# PT100.net
KiCad netlist of a schematic drawn in Altium Designer
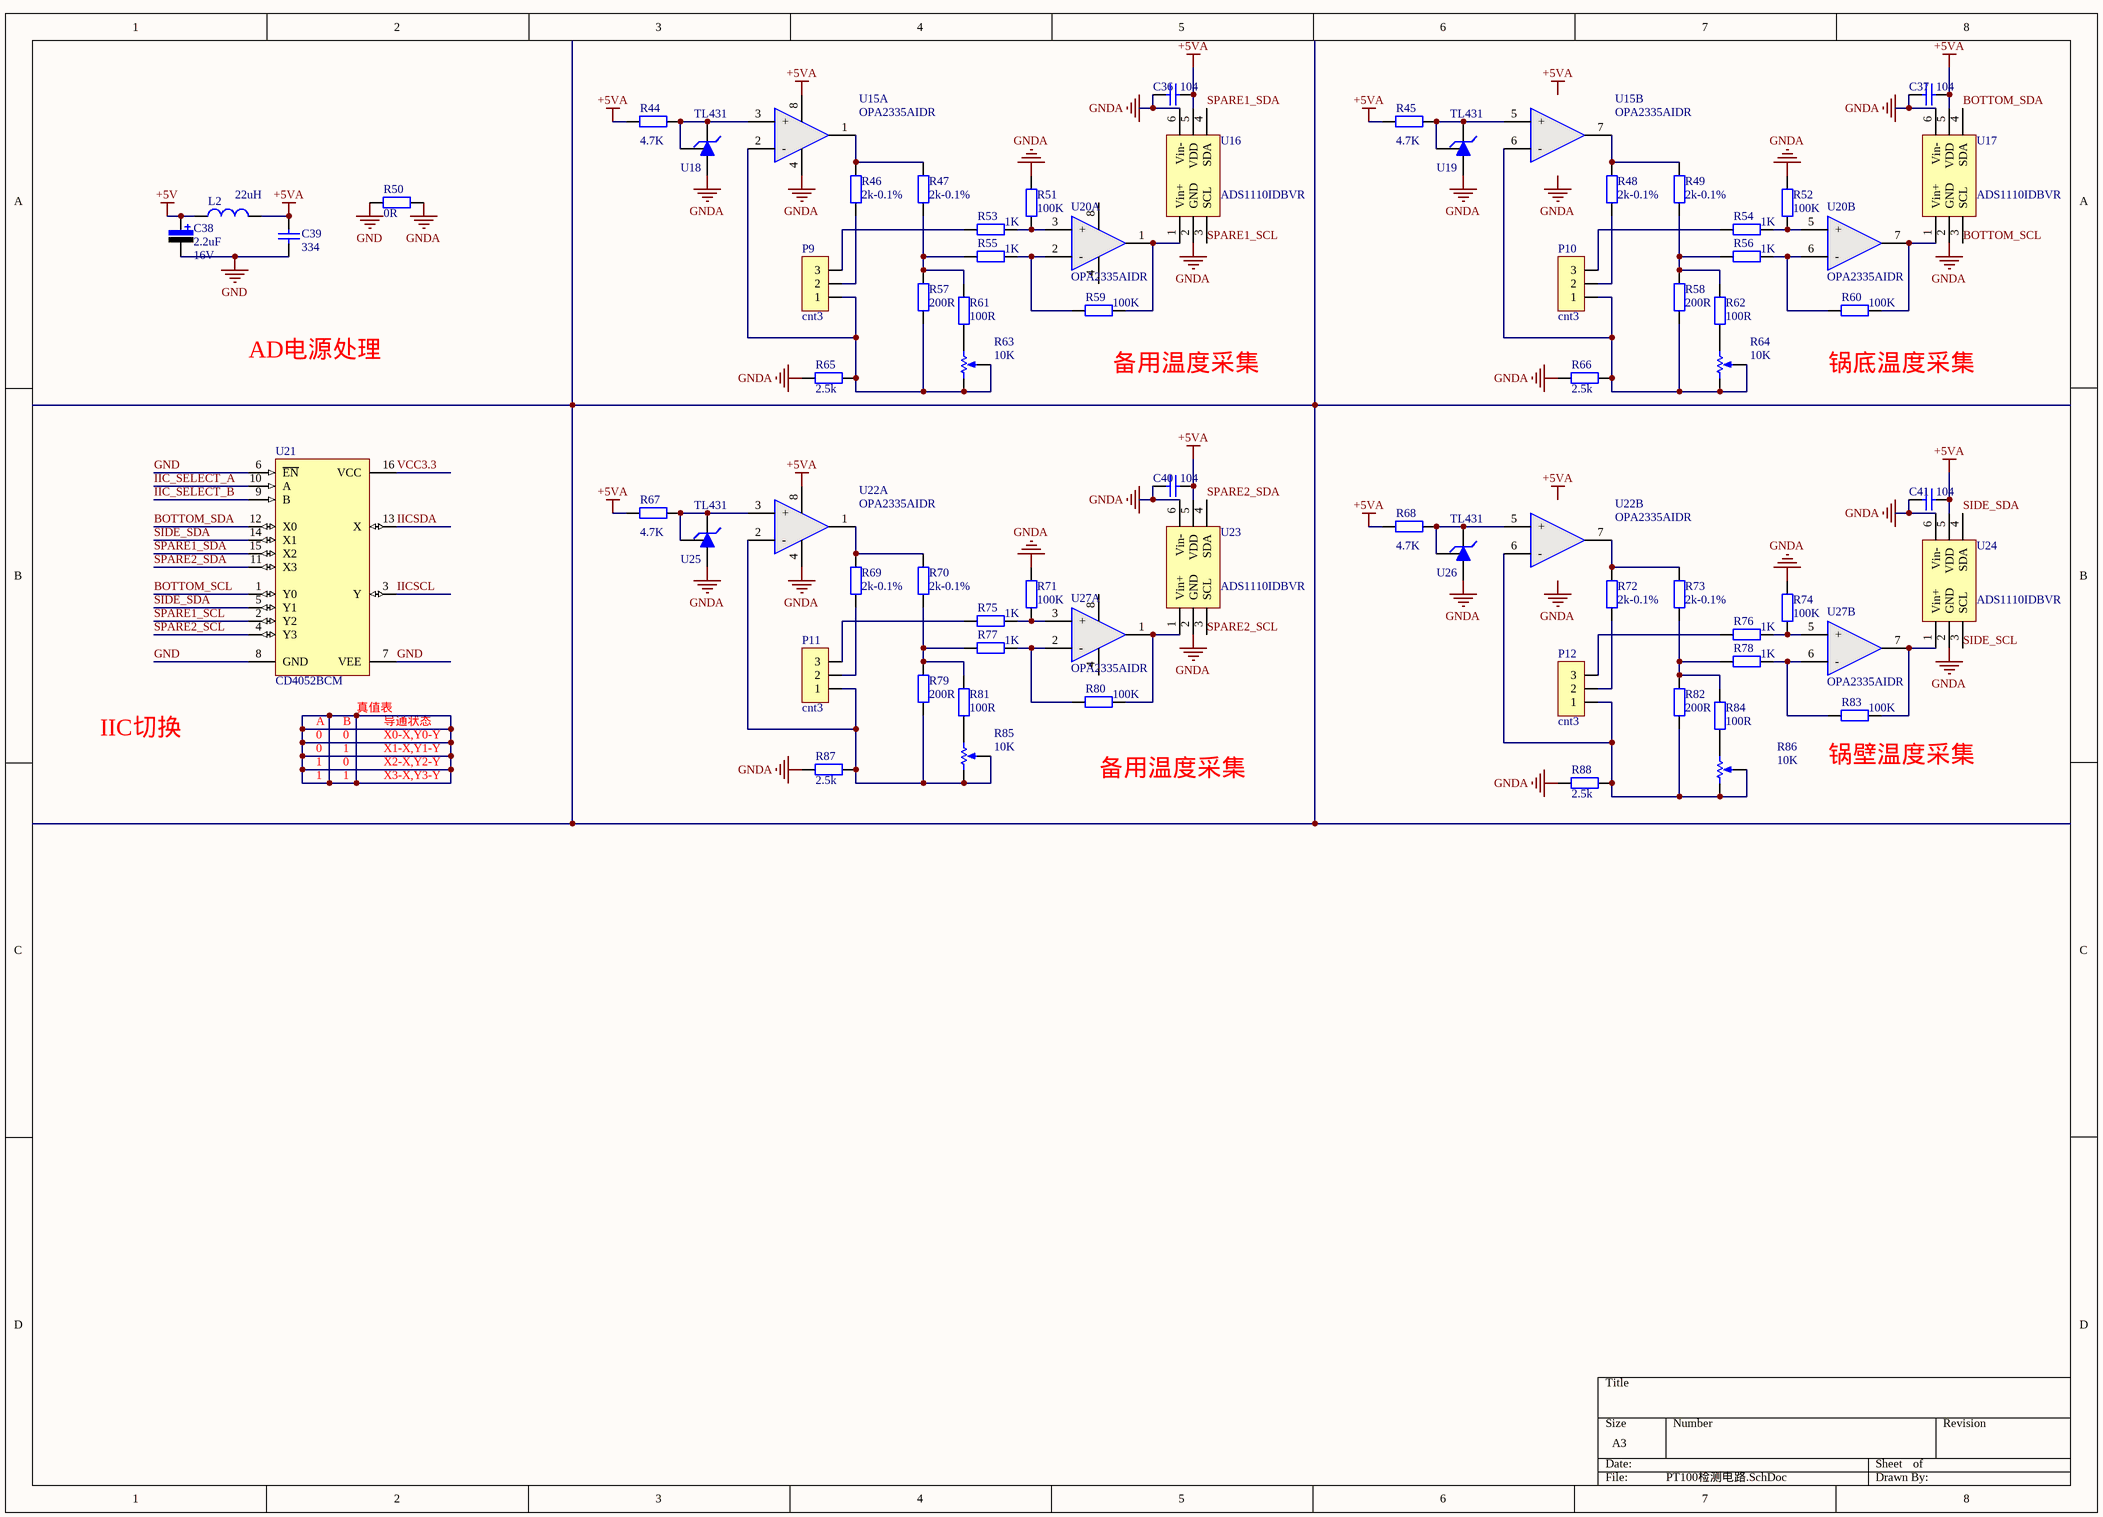
[diagram p0: PT100检测电路.SchDoc]

(export (version "E")
  (design (tool "Eeschema 10.0.6"))
  (components
    (comp (ref "C36")
      (value "104")
      (footprint "C-RAD-0603")
      (description "无极性电容")
      (fields (field (name "Comment") "Cap") (field (name "PUBLISHER") "Altium Limited"))
      (libsource (lib "Fszhang") (part "Cap"))
    )
    (comp (ref "C37")
      (value "104")
      (footprint "C-RAD-0603")
      (description "无极性电容")
      (fields (field (name "Comment") "Cap") (field (name "PUBLISHER") "Altium Limited"))
      (libsource (lib "Fszhang") (part "Cap"))
    )
    (comp (ref "C38")
      (value "2.2uF")
      (footprint "CAP-3216")
      (description "极性电解电容")
      (fields
        (field (name "VOL") "16V")
        (field (name "Comment") "Cap Pol")
        (field (name "PUBLISHER") "Altium Limited")
      )
      (libsource (lib "Fszhang") (part "Cap Pol"))
    )
    (comp (ref "C39")
      (value "334")
      (footprint "C-RAD-0603")
      (description "无极性电容")
      (fields (field (name "Comment") "Cap") (field (name "PUBLISHER") "Altium Limited"))
      (libsource (lib "Fszhang") (part "Cap"))
    )
    (comp (ref "C40")
      (value "104")
      (footprint "C-RAD-0603")
      (description "无极性电容")
      (fields (field (name "Comment") "Cap") (field (name "PUBLISHER") "Altium Limited"))
      (libsource (lib "Fszhang") (part "Cap"))
    )
    (comp (ref "C41")
      (value "104")
      (footprint "C-RAD-0603")
      (description "无极性电容")
      (fields (field (name "Comment") "Cap") (field (name "PUBLISHER") "Altium Limited"))
      (libsource (lib "Fszhang") (part "Cap"))
    )
    (comp (ref "L2")
      (value "22uH")
      (footprint "1206")
      (description "电感")
      (fields (field (name "Comment") "Inductor") (field (name "PUBLISHER") "Altium Limited"))
      (libsource (lib "Fszhang") (part "Inductor"))
    )
    (comp (ref "P9")
      (value "cnt3")
      (footprint "7.62mmPCB接线端子3p")
      (description "3p接线端子")
      (libsource (lib "MY_Library") (part "cnt3"))
    )
    (comp (ref "P10")
      (value "cnt3")
      (footprint "7.62mmPCB接线端子3p")
      (description "3p接线端子")
      (libsource (lib "MY_Library") (part "cnt3"))
    )
    (comp (ref "P11")
      (value "cnt3")
      (footprint "7.62mmPCB接线端子3p")
      (description "3p接线端子")
      (libsource (lib "MY_Library") (part "cnt3"))
    )
    (comp (ref "P12")
      (value "cnt3")
      (footprint "7.62mmPCB接线端子3p")
      (description "3p接线端子")
      (libsource (lib "MY_Library") (part "cnt3"))
    )
    (comp (ref "R44")
      (value "4.7K")
      (footprint "0603-1")
      (description "贴片电阻")
      (fields (field (name "Comment") "Res1") (field (name "PUBLISHER") "Altium Limited"))
      (libsource (lib "") (part "Res1_1"))
    )
    (comp (ref "R45")
      (value "4.7K")
      (footprint "0603-1")
      (description "贴片电阻")
      (fields (field (name "Comment") "Res1") (field (name "PUBLISHER") "Altium Limited"))
      (libsource (lib "") (part "Res1_1"))
    )
    (comp (ref "R46")
      (value "2k-0.1%")
      (footprint "0603-1")
      (description "贴片电阻")
      (fields (field (name "Comment") "Res1") (field (name "PUBLISHER") "Altium Limited"))
      (libsource (lib "Fszhang") (part "Res1"))
    )
    (comp (ref "R47")
      (value "2k-0.1%")
      (footprint "0603-1")
      (description "贴片电阻")
      (fields (field (name "Comment") "Res1") (field (name "PUBLISHER") "Altium Limited"))
      (libsource (lib "Fszhang") (part "Res1"))
    )
    (comp (ref "R48")
      (value "2k-0.1%")
      (footprint "0603-1")
      (description "贴片电阻")
      (fields (field (name "Comment") "Res1") (field (name "PUBLISHER") "Altium Limited"))
      (libsource (lib "Fszhang") (part "Res1"))
    )
    (comp (ref "R49")
      (value "2k-0.1%")
      (footprint "0603-1")
      (description "贴片电阻")
      (fields (field (name "Comment") "Res1") (field (name "PUBLISHER") "Altium Limited"))
      (libsource (lib "Fszhang") (part "Res1"))
    )
    (comp (ref "R50")
      (value "0R")
      (footprint "0603-1")
      (description "贴片电阻")
      (fields (field (name "Comment") "Res1") (field (name "PUBLISHER") "Altium Limited"))
      (libsource (lib "") (part "Res1_2"))
    )
    (comp (ref "R51")
      (value "100K")
      (footprint "0603-1")
      (description "贴片电阻")
      (fields (field (name "Comment") "Res1") (field (name "PUBLISHER") "Altium Limited"))
      (libsource (lib "Fszhang") (part "Res1"))
    )
    (comp (ref "R52")
      (value "100K")
      (footprint "0603-1")
      (description "贴片电阻")
      (fields (field (name "Comment") "Res1") (field (name "PUBLISHER") "Altium Limited"))
      (libsource (lib "Fszhang") (part "Res1"))
    )
    (comp (ref "R53")
      (value "1K")
      (footprint "0603-1")
      (description "贴片电阻")
      (fields (field (name "Comment") "Res1") (field (name "PUBLISHER") "Altium Limited"))
      (libsource (lib "") (part "Res1_1"))
    )
    (comp (ref "R54")
      (value "1K")
      (footprint "0603-1")
      (description "贴片电阻")
      (fields (field (name "Comment") "Res1") (field (name "PUBLISHER") "Altium Limited"))
      (libsource (lib "") (part "Res1_1"))
    )
    (comp (ref "R55")
      (value "1K")
      (footprint "0603-1")
      (description "贴片电阻")
      (fields (field (name "Comment") "Res1") (field (name "PUBLISHER") "Altium Limited"))
      (libsource (lib "") (part "Res1_1"))
    )
    (comp (ref "R56")
      (value "1K")
      (footprint "0603-1")
      (description "贴片电阻")
      (fields (field (name "Comment") "Res1") (field (name "PUBLISHER") "Altium Limited"))
      (libsource (lib "") (part "Res1_1"))
    )
    (comp (ref "R57")
      (value "200R")
      (footprint "0603-1")
      (description "贴片电阻")
      (fields (field (name "Comment") "Res1") (field (name "PUBLISHER") "Altium Limited"))
      (libsource (lib "Fszhang") (part "Res1"))
    )
    (comp (ref "R58")
      (value "200R")
      (footprint "0603-1")
      (description "贴片电阻")
      (fields (field (name "Comment") "Res1") (field (name "PUBLISHER") "Altium Limited"))
      (libsource (lib "Fszhang") (part "Res1"))
    )
    (comp (ref "R59")
      (value "100K")
      (footprint "0603-1")
      (description "贴片电阻")
      (fields (field (name "Comment") "Res1") (field (name "PUBLISHER") "Altium Limited"))
      (libsource (lib "") (part "Res1_1"))
    )
    (comp (ref "R60")
      (value "100K")
      (footprint "0603-1")
      (description "贴片电阻")
      (fields (field (name "Comment") "Res1") (field (name "PUBLISHER") "Altium Limited"))
      (libsource (lib "") (part "Res1_1"))
    )
    (comp (ref "R61")
      (value "100R")
      (footprint "0603-1")
      (description "贴片电阻")
      (fields (field (name "Comment") "Res1") (field (name "PUBLISHER") "Altium Limited"))
      (libsource (lib "Fszhang") (part "Res1"))
    )
    (comp (ref "R62")
      (value "100R")
      (footprint "0603-1")
      (description "贴片电阻")
      (fields (field (name "Comment") "Res1") (field (name "PUBLISHER") "Altium Limited"))
      (libsource (lib "Fszhang") (part "Res1"))
    )
    (comp (ref "R63")
      (value "10K")
      (footprint "VR-3266W")
      (description "精密可调电阻")
      (fields (field (name "Comment") "RPot") (field (name "PUBLISHER") "Altium Limited"))
      (libsource (lib "Fszhang") (part "RPot"))
    )
    (comp (ref "R64")
      (value "10K")
      (footprint "VR-3266W")
      (description "精密可调电阻")
      (fields (field (name "Comment") "RPot") (field (name "PUBLISHER") "Altium Limited"))
      (libsource (lib "Fszhang") (part "RPot"))
    )
    (comp (ref "R65")
      (value "2.5k")
      (footprint "0603-1")
      (description "贴片电阻")
      (fields (field (name "Comment") "Res1") (field (name "PUBLISHER") "Altium Limited"))
      (libsource (lib "") (part "Res1_1"))
    )
    (comp (ref "R66")
      (value "2.5k")
      (footprint "0603-1")
      (description "贴片电阻")
      (fields (field (name "Comment") "Res1") (field (name "PUBLISHER") "Altium Limited"))
      (libsource (lib "") (part "Res1_1"))
    )
    (comp (ref "R67")
      (value "4.7K")
      (footprint "0603-1")
      (description "贴片电阻")
      (fields (field (name "Comment") "Res1") (field (name "PUBLISHER") "Altium Limited"))
      (libsource (lib "") (part "Res1_1"))
    )
    (comp (ref "R68")
      (value "4.7K")
      (footprint "0603-1")
      (description "贴片电阻")
      (fields (field (name "Comment") "Res1") (field (name "PUBLISHER") "Altium Limited"))
      (libsource (lib "") (part "Res1_1"))
    )
    (comp (ref "R69")
      (value "2k-0.1%")
      (footprint "0603-1")
      (description "贴片电阻")
      (fields (field (name "Comment") "Res1") (field (name "PUBLISHER") "Altium Limited"))
      (libsource (lib "Fszhang") (part "Res1"))
    )
    (comp (ref "R70")
      (value "2k-0.1%")
      (footprint "0603-1")
      (description "贴片电阻")
      (fields (field (name "Comment") "Res1") (field (name "PUBLISHER") "Altium Limited"))
      (libsource (lib "Fszhang") (part "Res1"))
    )
    (comp (ref "R71")
      (value "100K")
      (footprint "0603-1")
      (description "贴片电阻")
      (fields (field (name "Comment") "Res1") (field (name "PUBLISHER") "Altium Limited"))
      (libsource (lib "Fszhang") (part "Res1"))
    )
    (comp (ref "R72")
      (value "2k-0.1%")
      (footprint "0603-1")
      (description "贴片电阻")
      (fields (field (name "Comment") "Res1") (field (name "PUBLISHER") "Altium Limited"))
      (libsource (lib "Fszhang") (part "Res1"))
    )
    (comp (ref "R73")
      (value "2k-0.1%")
      (footprint "0603-1")
      (description "贴片电阻")
      (fields (field (name "Comment") "Res1") (field (name "PUBLISHER") "Altium Limited"))
      (libsource (lib "Fszhang") (part "Res1"))
    )
    (comp (ref "R74")
      (value "100K")
      (footprint "0603-1")
      (description "贴片电阻")
      (fields (field (name "Comment") "Res1") (field (name "PUBLISHER") "Altium Limited"))
      (libsource (lib "Fszhang") (part "Res1"))
    )
    (comp (ref "R75")
      (value "1K")
      (footprint "0603-1")
      (description "贴片电阻")
      (fields (field (name "Comment") "Res1") (field (name "PUBLISHER") "Altium Limited"))
      (libsource (lib "") (part "Res1_1"))
    )
    (comp (ref "R76")
      (value "1K")
      (footprint "0603-1")
      (description "贴片电阻")
      (fields (field (name "Comment") "Res1") (field (name "PUBLISHER") "Altium Limited"))
      (libsource (lib "") (part "Res1_1"))
    )
    (comp (ref "R77")
      (value "1K")
      (footprint "0603-1")
      (description "贴片电阻")
      (fields (field (name "Comment") "Res1") (field (name "PUBLISHER") "Altium Limited"))
      (libsource (lib "") (part "Res1_1"))
    )
    (comp (ref "R78")
      (value "1K")
      (footprint "0603-1")
      (description "贴片电阻")
      (fields (field (name "Comment") "Res1") (field (name "PUBLISHER") "Altium Limited"))
      (libsource (lib "") (part "Res1_1"))
    )
    (comp (ref "R79")
      (value "200R")
      (footprint "0603-1")
      (description "贴片电阻")
      (fields (field (name "Comment") "Res1") (field (name "PUBLISHER") "Altium Limited"))
      (libsource (lib "Fszhang") (part "Res1"))
    )
    (comp (ref "R80")
      (value "100K")
      (footprint "0603-1")
      (description "贴片电阻")
      (fields (field (name "Comment") "Res1") (field (name "PUBLISHER") "Altium Limited"))
      (libsource (lib "") (part "Res1_1"))
    )
    (comp (ref "R81")
      (value "100R")
      (footprint "0603-1")
      (description "贴片电阻")
      (fields (field (name "Comment") "Res1") (field (name "PUBLISHER") "Altium Limited"))
      (libsource (lib "Fszhang") (part "Res1"))
    )
    (comp (ref "R82")
      (value "200R")
      (footprint "0603-1")
      (description "贴片电阻")
      (fields (field (name "Comment") "Res1") (field (name "PUBLISHER") "Altium Limited"))
      (libsource (lib "Fszhang") (part "Res1"))
    )
    (comp (ref "R83")
      (value "100K")
      (footprint "0603-1")
      (description "贴片电阻")
      (fields (field (name "Comment") "Res1") (field (name "PUBLISHER") "Altium Limited"))
      (libsource (lib "") (part "Res1_1"))
    )
    (comp (ref "R84")
      (value "100R")
      (footprint "0603-1")
      (description "贴片电阻")
      (fields (field (name "Comment") "Res1") (field (name "PUBLISHER") "Altium Limited"))
      (libsource (lib "Fszhang") (part "Res1"))
    )
    (comp (ref "R85")
      (value "10K")
      (footprint "VR-3266W")
      (description "精密可调电阻")
      (fields (field (name "Comment") "RPot") (field (name "PUBLISHER") "Altium Limited"))
      (libsource (lib "Fszhang") (part "RPot"))
    )
    (comp (ref "R86")
      (value "10K")
      (footprint "VR-3266W")
      (description "精密可调电阻")
      (fields (field (name "Comment") "RPot") (field (name "PUBLISHER") "Altium Limited"))
      (libsource (lib "Fszhang") (part "RPot"))
    )
    (comp (ref "R87")
      (value "2.5k")
      (footprint "0603-1")
      (description "贴片电阻")
      (fields (field (name "Comment") "Res1") (field (name "PUBLISHER") "Altium Limited"))
      (libsource (lib "") (part "Res1_1"))
    )
    (comp (ref "R88")
      (value "2.5k")
      (footprint "0603-1")
      (description "贴片电阻")
      (fields (field (name "Comment") "Res1") (field (name "PUBLISHER") "Altium Limited"))
      (libsource (lib "") (part "Res1_1"))
    )
    (comp (ref "U15")
      (value "OPA2335AIDR")
      (footprint "NSO8_N")
      (description "双运放")
      (libsource (lib "Fszhang") (part "AD8667"))
    )
    (comp (ref "U16")
      (value "ADS1110IDBVR")
      (footprint "SOT23-6")
      (description "16位内部基准AD芯片IIC")
      (libsource (lib "Fszhang") (part "ADS1110IDBVR"))
    )
    (comp (ref "U17")
      (value "ADS1110IDBVR")
      (footprint "SOT23-6")
      (description "16位内部基准AD芯片IIC")
      (libsource (lib "Fszhang") (part "ADS1110IDBVR"))
    )
    (comp (ref "U18") (value "TL431") (footprint "SOT23") (libsource (lib "MY_Library") (part "TL431")))
    (comp (ref "U19") (value "TL431") (footprint "SOT23") (libsource (lib "MY_Library") (part "TL431")))
    (comp (ref "U20")
      (value "OPA2335AIDR")
      (footprint "NSO8_N")
      (description "双运放")
      (libsource (lib "Fszhang") (part "AD8667"))
    )
    (comp (ref "U21")
      (value "CD4052BCM")
      (footprint "NSO16_M")
      (description "双通道模拟开关")
      (fields (field (name "PUBLISHER") "Altium Limited"))
      (libsource (lib "Fszhang") (part "CD4052BCM"))
    )
    (comp (ref "U22")
      (value "OPA2335AIDR")
      (footprint "NSO8_N")
      (description "双运放")
      (libsource (lib "Fszhang") (part "AD8667"))
    )
    (comp (ref "U23")
      (value "ADS1110IDBVR")
      (footprint "SOT23-6")
      (description "16位内部基准AD芯片IIC")
      (libsource (lib "Fszhang") (part "ADS1110IDBVR"))
    )
    (comp (ref "U24")
      (value "ADS1110IDBVR")
      (footprint "SOT23-6")
      (description "16位内部基准AD芯片IIC")
      (libsource (lib "Fszhang") (part "ADS1110IDBVR"))
    )
    (comp (ref "U25") (value "TL431") (footprint "SOT23") (libsource (lib "MY_Library") (part "TL431")))
    (comp (ref "U26") (value "TL431") (footprint "SOT23") (libsource (lib "MY_Library") (part "TL431")))
    (comp (ref "U27")
      (value "OPA2335AIDR")
      (footprint "NSO8_N")
      (description "双运放")
      (libsource (lib "Fszhang") (part "AD8667"))
    )
  )
  (nets
    (net (code "1") (name "+5V") (class "Default")
      (node (ref "C38") (pin "1") (pinfunction "1_1") (pintype "passive"))
      (node (ref "L2") (pin "1") (pinfunction "1_1") (pintype "passive"))
    )
    (net (code "2") (name "+5VA") (class "Default")
      (node (ref "C36") (pin "2") (pinfunction "2_2") (pintype "passive"))
      (node (ref "C37") (pin "2") (pinfunction "2_2") (pintype "passive"))
      (node (ref "C39") (pin "1") (pinfunction "1_1") (pintype "passive"))
      (node (ref "C40") (pin "2") (pinfunction "2_2") (pintype "passive"))
      (node (ref "C41") (pin "2") (pinfunction "2_2") (pintype "passive"))
      (node (ref "L2") (pin "2") (pinfunction "2_2") (pintype "passive"))
      (node (ref "R44") (pin "1") (pinfunction "1_1") (pintype "passive"))
      (node (ref "R45") (pin "1") (pinfunction "1_1") (pintype "passive"))
      (node (ref "R67") (pin "1") (pinfunction "1_1") (pintype "passive"))
      (node (ref "R68") (pin "1") (pinfunction "1_1") (pintype "passive"))
      (node (ref "U15") (pin "8") (pinfunction "V+_8") (pintype "power_in"))
      (node (ref "U16") (pin "5") (pinfunction "VDD_5") (pintype "passive"))
      (node (ref "U17") (pin "5") (pinfunction "VDD_5") (pintype "passive"))
      (node (ref "U22") (pin "8") (pinfunction "V+_8") (pintype "power_in"))
      (node (ref "U23") (pin "5") (pinfunction "VDD_5") (pintype "passive"))
      (node (ref "U24") (pin "5") (pinfunction "VDD_5") (pintype "passive"))
    )
    (net (code "3") (name "/BOTTOM_SCL") (class "Default")
      (node (ref "U17") (pin "3") (pinfunction "SCL_3") (pintype "passive"))
      (node (ref "U21") (pin "1") (pinfunction "Y0_1") (pintype "bidirectional"))
    )
    (net (code "4") (name "/BOTTOM_SDA") (class "Default")
      (node (ref "U17") (pin "4") (pinfunction "SDA_4") (pintype "passive"))
      (node (ref "U21") (pin "12") (pinfunction "X0_12") (pintype "bidirectional"))
    )
    (net (code "5") (name "/IICSCL") (class "Default")
      (node (ref "U21") (pin "3") (pinfunction "Y_3") (pintype "bidirectional"))
    )
    (net (code "6") (name "/IICSDA") (class "Default")
      (node (ref "U21") (pin "13") (pinfunction "X_13") (pintype "bidirectional"))
    )
    (net (code "7") (name "/IIC_SELECT_A") (class "Default")
      (node (ref "U21") (pin "10") (pinfunction "A_10") (pintype "input"))
    )
    (net (code "8") (name "/IIC_SELECT_B") (class "Default")
      (node (ref "U21") (pin "9") (pinfunction "B_9") (pintype "input"))
    )
    (net (code "9") (name "/SIDE_SCL") (class "Default")
      (node (ref "U24") (pin "3") (pinfunction "SCL_3") (pintype "passive"))
    )
    (net (code "10") (name "/SIDE_SDA") (class "Default")
      (node (ref "U21") (pin "14") (pinfunction "X1_14") (pintype "bidirectional"))
      (node (ref "U21") (pin "5") (pinfunction "Y1_5") (pintype "bidirectional"))
      (node (ref "U24") (pin "4") (pinfunction "SDA_4") (pintype "passive"))
    )
    (net (code "11") (name "/SPARE1_SCL") (class "Default")
      (node (ref "U16") (pin "3") (pinfunction "SCL_3") (pintype "passive"))
      (node (ref "U21") (pin "2") (pinfunction "Y2_2") (pintype "bidirectional"))
    )
    (net (code "12") (name "/SPARE1_SDA") (class "Default")
      (node (ref "U16") (pin "4") (pinfunction "SDA_4") (pintype "passive"))
      (node (ref "U21") (pin "15") (pinfunction "X2_15") (pintype "bidirectional"))
    )
    (net (code "13") (name "/SPARE2_SCL") (class "Default")
      (node (ref "U21") (pin "4") (pinfunction "Y3_4") (pintype "bidirectional"))
      (node (ref "U23") (pin "3") (pinfunction "SCL_3") (pintype "passive"))
    )
    (net (code "14") (name "/SPARE2_SDA") (class "Default")
      (node (ref "U21") (pin "11") (pinfunction "X3_11") (pintype "bidirectional"))
      (node (ref "U23") (pin "4") (pinfunction "SDA_4") (pintype "passive"))
    )
    (net (code "15") (name "/VCC3.3") (class "Default")
      (node (ref "U21") (pin "16") (pinfunction "VCC_16") (pintype "power_in"))
    )
    (net (code "16") (name "GND") (class "Default")
      (node (ref "C38") (pin "2") (pinfunction "2_2") (pintype "passive"))
      (node (ref "C39") (pin "2") (pinfunction "2_2") (pintype "passive"))
      (node (ref "R50") (pin "2") (pinfunction "2_2") (pintype "passive"))
      (node (ref "U21") (pin "6") (pinfunction "~{EN}_6") (pintype "input"))
      (node (ref "U21") (pin "7") (pinfunction "VEE_7") (pintype "power_in"))
      (node (ref "U21") (pin "8") (pinfunction "GND_8") (pintype "power_in"))
    )
    (net (code "17") (name "GNDA") (class "Default")
      (node (ref "C36") (pin "1") (pinfunction "1_1") (pintype "passive"))
      (node (ref "C37") (pin "1") (pinfunction "1_1") (pintype "passive"))
      (node (ref "C40") (pin "1") (pinfunction "1_1") (pintype "passive"))
      (node (ref "C41") (pin "1") (pinfunction "1_1") (pintype "passive"))
      (node (ref "R50") (pin "1") (pinfunction "1_1") (pintype "passive"))
      (node (ref "R51") (pin "2") (pinfunction "2_2") (pintype "passive"))
      (node (ref "R52") (pin "2") (pinfunction "2_2") (pintype "passive"))
      (node (ref "R65") (pin "1") (pinfunction "1_1") (pintype "passive"))
      (node (ref "R66") (pin "1") (pinfunction "1_1") (pintype "passive"))
      (node (ref "R71") (pin "2") (pinfunction "2_2") (pintype "passive"))
      (node (ref "R74") (pin "2") (pinfunction "2_2") (pintype "passive"))
      (node (ref "R87") (pin "1") (pinfunction "1_1") (pintype "passive"))
      (node (ref "R88") (pin "1") (pinfunction "1_1") (pintype "passive"))
      (node (ref "U15") (pin "4") (pinfunction "V-_4") (pintype "power_in"))
      (node (ref "U16") (pin "2") (pinfunction "GND_2") (pintype "passive"))
      (node (ref "U16") (pin "6") (pinfunction "Vin-_6") (pintype "passive"))
      (node (ref "U17") (pin "2") (pinfunction "GND_2") (pintype "passive"))
      (node (ref "U17") (pin "6") (pinfunction "Vin-_6") (pintype "passive"))
      (node (ref "U18") (pin "3") (pinfunction "3_3") (pintype "passive"))
      (node (ref "U19") (pin "3") (pinfunction "3_3") (pintype "passive"))
      (node (ref "U22") (pin "4") (pinfunction "V-_4") (pintype "power_in"))
      (node (ref "U23") (pin "2") (pinfunction "GND_2") (pintype "passive"))
      (node (ref "U23") (pin "6") (pinfunction "Vin-_6") (pintype "passive"))
      (node (ref "U24") (pin "2") (pinfunction "GND_2") (pintype "passive"))
      (node (ref "U24") (pin "6") (pinfunction "Vin-_6") (pintype "passive"))
      (node (ref "U25") (pin "3") (pinfunction "3_3") (pintype "passive"))
      (node (ref "U26") (pin "3") (pinfunction "3_3") (pintype "passive"))
    )
    (net (code "18") (name "Net-(P9-Pad2)") (class "Default")
      (node (ref "P9") (pin "2") (pinfunction "2_2") (pintype "passive"))
      (node (ref "R46") (pin "1") (pinfunction "1_1") (pintype "passive"))
    )
    (net (code "19") (name "Net-(P9-Pad3)") (class "Default")
      (node (ref "P9") (pin "3") (pinfunction "3_3") (pintype "passive"))
      (node (ref "R53") (pin "1") (pinfunction "1_1") (pintype "passive"))
    )
    (net (code "20") (name "Net-(P10-Pad2)") (class "Default")
      (node (ref "P10") (pin "2") (pinfunction "2_2") (pintype "passive"))
      (node (ref "R48") (pin "1") (pinfunction "1_1") (pintype "passive"))
    )
    (net (code "21") (name "Net-(P10-Pad3)") (class "Default")
      (node (ref "P10") (pin "3") (pinfunction "3_3") (pintype "passive"))
      (node (ref "R54") (pin "1") (pinfunction "1_1") (pintype "passive"))
    )
    (net (code "22") (name "Net-(P11-Pad2)") (class "Default")
      (node (ref "P11") (pin "2") (pinfunction "2_2") (pintype "passive"))
      (node (ref "R69") (pin "1") (pinfunction "1_1") (pintype "passive"))
    )
    (net (code "23") (name "Net-(P11-Pad3)") (class "Default")
      (node (ref "P11") (pin "3") (pinfunction "3_3") (pintype "passive"))
      (node (ref "R75") (pin "1") (pinfunction "1_1") (pintype "passive"))
    )
    (net (code "24") (name "Net-(P12-Pad2)") (class "Default")
      (node (ref "P12") (pin "2") (pinfunction "2_2") (pintype "passive"))
      (node (ref "R72") (pin "1") (pinfunction "1_1") (pintype "passive"))
    )
    (net (code "25") (name "Net-(P12-Pad3)") (class "Default")
      (node (ref "P12") (pin "3") (pinfunction "3_3") (pintype "passive"))
      (node (ref "R76") (pin "1") (pinfunction "1_1") (pintype "passive"))
    )
    (net (code "26") (name "Net-(R47-Pad1)") (class "Default")
      (node (ref "R47") (pin "1") (pinfunction "1_1") (pintype "passive"))
      (node (ref "R55") (pin "1") (pinfunction "1_1") (pintype "passive"))
      (node (ref "R57") (pin "2") (pinfunction "2_2") (pintype "passive"))
      (node (ref "R61") (pin "2") (pinfunction "2_2") (pintype "passive"))
    )
    (net (code "27") (name "Net-(R49-Pad1)") (class "Default")
      (node (ref "R49") (pin "1") (pinfunction "1_1") (pintype "passive"))
      (node (ref "R56") (pin "1") (pinfunction "1_1") (pintype "passive"))
      (node (ref "R58") (pin "2") (pinfunction "2_2") (pintype "passive"))
      (node (ref "R62") (pin "2") (pinfunction "2_2") (pintype "passive"))
    )
    (net (code "28") (name "Net-(R63-BOT)") (class "Default")
      (node (ref "R61") (pin "1") (pinfunction "1_1") (pintype "passive"))
      (node (ref "R63") (pin "3") (pinfunction "BOT_3") (pintype "passive"))
    )
    (net (code "29") (name "Net-(R63-TAP)") (class "Default")
      (node (ref "P9") (pin "1") (pinfunction "1_1") (pintype "passive"))
      (node (ref "R57") (pin "1") (pinfunction "1_1") (pintype "passive"))
      (node (ref "R63") (pin "1") (pinfunction "TOP_1") (pintype "passive"))
      (node (ref "R63") (pin "2") (pinfunction "TAP_2") (pintype "passive"))
      (node (ref "R65") (pin "2") (pinfunction "2_2") (pintype "passive"))
      (node (ref "U15") (pin "2") (pinfunction "-_2") (pintype "passive"))
    )
    (net (code "30") (name "Net-(R64-BOT)") (class "Default")
      (node (ref "R62") (pin "1") (pinfunction "1_1") (pintype "passive"))
      (node (ref "R64") (pin "3") (pinfunction "BOT_3") (pintype "passive"))
    )
    (net (code "31") (name "Net-(R64-TAP)") (class "Default")
      (node (ref "P10") (pin "1") (pinfunction "1_1") (pintype "passive"))
      (node (ref "R58") (pin "1") (pinfunction "1_1") (pintype "passive"))
      (node (ref "R64") (pin "1") (pinfunction "TOP_1") (pintype "passive"))
      (node (ref "R64") (pin "2") (pinfunction "TAP_2") (pintype "passive"))
      (node (ref "R66") (pin "2") (pinfunction "2_2") (pintype "passive"))
      (node (ref "U15") (pin "6") (pinfunction "-_6") (pintype "passive"))
    )
    (net (code "32") (name "Net-(R70-Pad1)") (class "Default")
      (node (ref "R70") (pin "1") (pinfunction "1_1") (pintype "passive"))
      (node (ref "R77") (pin "1") (pinfunction "1_1") (pintype "passive"))
      (node (ref "R79") (pin "2") (pinfunction "2_2") (pintype "passive"))
      (node (ref "R81") (pin "2") (pinfunction "2_2") (pintype "passive"))
    )
    (net (code "33") (name "Net-(R73-Pad1)") (class "Default")
      (node (ref "R73") (pin "1") (pinfunction "1_1") (pintype "passive"))
      (node (ref "R78") (pin "1") (pinfunction "1_1") (pintype "passive"))
      (node (ref "R82") (pin "2") (pinfunction "2_2") (pintype "passive"))
      (node (ref "R84") (pin "2") (pinfunction "2_2") (pintype "passive"))
    )
    (net (code "34") (name "Net-(R85-BOT)") (class "Default")
      (node (ref "R81") (pin "1") (pinfunction "1_1") (pintype "passive"))
      (node (ref "R85") (pin "3") (pinfunction "BOT_3") (pintype "passive"))
    )
    (net (code "35") (name "Net-(R85-TAP)") (class "Default")
      (node (ref "P11") (pin "1") (pinfunction "1_1") (pintype "passive"))
      (node (ref "R79") (pin "1") (pinfunction "1_1") (pintype "passive"))
      (node (ref "R85") (pin "1") (pinfunction "TOP_1") (pintype "passive"))
      (node (ref "R85") (pin "2") (pinfunction "TAP_2") (pintype "passive"))
      (node (ref "R87") (pin "2") (pinfunction "2_2") (pintype "passive"))
      (node (ref "U22") (pin "2") (pinfunction "-_2") (pintype "passive"))
    )
    (net (code "36") (name "Net-(R86-BOT)") (class "Default")
      (node (ref "R84") (pin "1") (pinfunction "1_1") (pintype "passive"))
      (node (ref "R86") (pin "3") (pinfunction "BOT_3") (pintype "passive"))
    )
    (net (code "37") (name "Net-(R86-TAP)") (class "Default")
      (node (ref "P12") (pin "1") (pinfunction "1_1") (pintype "passive"))
      (node (ref "R82") (pin "1") (pinfunction "1_1") (pintype "passive"))
      (node (ref "R86") (pin "1") (pinfunction "TOP_1") (pintype "passive"))
      (node (ref "R86") (pin "2") (pinfunction "TAP_2") (pintype "passive"))
      (node (ref "R88") (pin "2") (pinfunction "2_2") (pintype "passive"))
      (node (ref "U22") (pin "6") (pinfunction "-_6") (pintype "passive"))
    )
    (net (code "38") (name "Net-(U15A-+)") (class "Default")
      (node (ref "R44") (pin "2") (pinfunction "2_2") (pintype "passive"))
      (node (ref "U15") (pin "3") (pinfunction "+_3") (pintype "passive"))
      (node (ref "U18") (pin "1") (pinfunction "1_1") (pintype "passive"))
      (node (ref "U18") (pin "2") (pinfunction "2_2") (pintype "passive"))
    )
    (net (code "39") (name "Net-(U15A-OUT1)") (class "Default")
      (node (ref "R46") (pin "2") (pinfunction "2_2") (pintype "passive"))
      (node (ref "R47") (pin "2") (pinfunction "2_2") (pintype "passive"))
      (node (ref "U15") (pin "1") (pinfunction "OUT1_1") (pintype "passive"))
    )
    (net (code "40") (name "Net-(U15B-+)") (class "Default")
      (node (ref "R45") (pin "2") (pinfunction "2_2") (pintype "passive"))
      (node (ref "U15") (pin "5") (pinfunction "+_5") (pintype "passive"))
      (node (ref "U19") (pin "1") (pinfunction "1_1") (pintype "passive"))
      (node (ref "U19") (pin "2") (pinfunction "2_2") (pintype "passive"))
    )
    (net (code "41") (name "Net-(U15B-OUT2)") (class "Default")
      (node (ref "R48") (pin "2") (pinfunction "2_2") (pintype "passive"))
      (node (ref "R49") (pin "2") (pinfunction "2_2") (pintype "passive"))
      (node (ref "U15") (pin "7") (pinfunction "OUT2_7") (pintype "passive"))
    )
    (net (code "42") (name "Net-(U16-Vin+)") (class "Default")
      (node (ref "R59") (pin "2") (pinfunction "2_2") (pintype "passive"))
      (node (ref "U16") (pin "1") (pinfunction "Vin+_1") (pintype "passive"))
      (node (ref "U20") (pin "1") (pinfunction "OUT1_1") (pintype "passive"))
    )
    (net (code "43") (name "Net-(U17-Vin+)") (class "Default")
      (node (ref "R60") (pin "2") (pinfunction "2_2") (pintype "passive"))
      (node (ref "U17") (pin "1") (pinfunction "Vin+_1") (pintype "passive"))
      (node (ref "U20") (pin "7") (pinfunction "OUT2_7") (pintype "passive"))
    )
    (net (code "44") (name "Net-(U20A-+)") (class "Default")
      (node (ref "R51") (pin "1") (pinfunction "1_1") (pintype "passive"))
      (node (ref "R53") (pin "2") (pinfunction "2_2") (pintype "passive"))
      (node (ref "U20") (pin "3") (pinfunction "+_3") (pintype "passive"))
    )
    (net (code "45") (name "Net-(U20A--)") (class "Default")
      (node (ref "R55") (pin "2") (pinfunction "2_2") (pintype "passive"))
      (node (ref "R59") (pin "1") (pinfunction "1_1") (pintype "passive"))
      (node (ref "U20") (pin "2") (pinfunction "-_2") (pintype "passive"))
    )
    (net (code "46") (name "Net-(U20B-+)") (class "Default")
      (node (ref "R52") (pin "1") (pinfunction "1_1") (pintype "passive"))
      (node (ref "R54") (pin "2") (pinfunction "2_2") (pintype "passive"))
      (node (ref "U20") (pin "5") (pinfunction "+_5") (pintype "passive"))
    )
    (net (code "47") (name "Net-(U20B--)") (class "Default")
      (node (ref "R56") (pin "2") (pinfunction "2_2") (pintype "passive"))
      (node (ref "R60") (pin "1") (pinfunction "1_1") (pintype "passive"))
      (node (ref "U20") (pin "6") (pinfunction "-_6") (pintype "passive"))
    )
    (net (code "48") (name "Net-(U22A-+)") (class "Default")
      (node (ref "R67") (pin "2") (pinfunction "2_2") (pintype "passive"))
      (node (ref "U22") (pin "3") (pinfunction "+_3") (pintype "passive"))
      (node (ref "U25") (pin "1") (pinfunction "1_1") (pintype "passive"))
      (node (ref "U25") (pin "2") (pinfunction "2_2") (pintype "passive"))
    )
    (net (code "49") (name "Net-(U22A-OUT1)") (class "Default")
      (node (ref "R69") (pin "2") (pinfunction "2_2") (pintype "passive"))
      (node (ref "R70") (pin "2") (pinfunction "2_2") (pintype "passive"))
      (node (ref "U22") (pin "1") (pinfunction "OUT1_1") (pintype "passive"))
    )
    (net (code "50") (name "Net-(U22B-+)") (class "Default")
      (node (ref "R68") (pin "2") (pinfunction "2_2") (pintype "passive"))
      (node (ref "U22") (pin "5") (pinfunction "+_5") (pintype "passive"))
      (node (ref "U26") (pin "1") (pinfunction "1_1") (pintype "passive"))
      (node (ref "U26") (pin "2") (pinfunction "2_2") (pintype "passive"))
    )
    (net (code "51") (name "Net-(U22B-OUT2)") (class "Default")
      (node (ref "R72") (pin "2") (pinfunction "2_2") (pintype "passive"))
      (node (ref "R73") (pin "2") (pinfunction "2_2") (pintype "passive"))
      (node (ref "U22") (pin "7") (pinfunction "OUT2_7") (pintype "passive"))
    )
    (net (code "52") (name "Net-(U23-Vin+)") (class "Default")
      (node (ref "R80") (pin "2") (pinfunction "2_2") (pintype "passive"))
      (node (ref "U23") (pin "1") (pinfunction "Vin+_1") (pintype "passive"))
      (node (ref "U27") (pin "1") (pinfunction "OUT1_1") (pintype "passive"))
    )
    (net (code "53") (name "Net-(U24-Vin+)") (class "Default")
      (node (ref "R83") (pin "2") (pinfunction "2_2") (pintype "passive"))
      (node (ref "U24") (pin "1") (pinfunction "Vin+_1") (pintype "passive"))
      (node (ref "U27") (pin "7") (pinfunction "OUT2_7") (pintype "passive"))
    )
    (net (code "54") (name "Net-(U27A-+)") (class "Default")
      (node (ref "R71") (pin "1") (pinfunction "1_1") (pintype "passive"))
      (node (ref "R75") (pin "2") (pinfunction "2_2") (pintype "passive"))
      (node (ref "U27") (pin "3") (pinfunction "+_3") (pintype "passive"))
    )
    (net (code "55") (name "Net-(U27A--)") (class "Default")
      (node (ref "R77") (pin "2") (pinfunction "2_2") (pintype "passive"))
      (node (ref "R80") (pin "1") (pinfunction "1_1") (pintype "passive"))
      (node (ref "U27") (pin "2") (pinfunction "-_2") (pintype "passive"))
    )
    (net (code "56") (name "Net-(U27B-+)") (class "Default")
      (node (ref "R74") (pin "1") (pinfunction "1_1") (pintype "passive"))
      (node (ref "R76") (pin "2") (pinfunction "2_2") (pintype "passive"))
      (node (ref "U27") (pin "5") (pinfunction "+_5") (pintype "passive"))
    )
    (net (code "57") (name "Net-(U27B--)") (class "Default")
      (node (ref "R78") (pin "2") (pinfunction "2_2") (pintype "passive"))
      (node (ref "R83") (pin "1") (pinfunction "1_1") (pintype "passive"))
      (node (ref "U27") (pin "6") (pinfunction "-_6") (pintype "passive"))
    )
    (net (code "58") (name "unconnected-(U20A-V+-Pad8)") (class "Default")
      (node (ref "U20") (pin "8") (pinfunction "V+_8") (pintype "power_in"))
    )
    (net (code "59") (name "unconnected-(U20A-V--Pad4)") (class "Default")
      (node (ref "U20") (pin "4") (pinfunction "V-_4") (pintype "power_in"))
    )
    (net (code "60") (name "unconnected-(U27A-V+-Pad8)") (class "Default")
      (node (ref "U27") (pin "8") (pinfunction "V+_8") (pintype "power_in"))
    )
    (net (code "61") (name "unconnected-(U27A-V--Pad4)") (class "Default")
      (node (ref "U27") (pin "4") (pinfunction "V-_4") (pintype "power_in"))
    )
  )
)
